# USB.net
KiCad netlist of a schematic drawn in Altium Designer
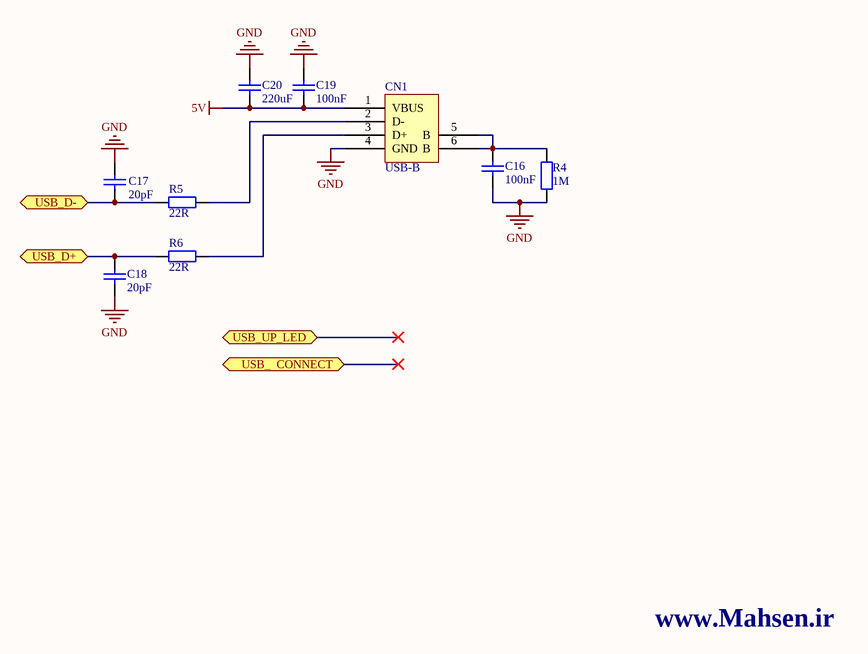
[diagram p0: USB.SchDoc]

(export (version "E")
  (design (tool "Eeschema 10.0.6"))
  (components
    (comp (ref "C16")
      (value "100nF")
      (footprint "0805")
      (description "Capacitor")
      (fields (field (name "PUBLISHER") "Altium Limited"))
      (libsource (lib "Miscellaneous Devices") (part "Cap"))
    )
    (comp (ref "C17")
      (value "20pF")
      (footprint "0805")
      (description "Capacitor")
      (fields (field (name "PUBLISHER") "Altium Limited"))
      (libsource (lib "Miscellaneous Devices") (part "Cap"))
    )
    (comp (ref "C18")
      (value "20pF")
      (footprint "0805")
      (description "Capacitor")
      (fields (field (name "PUBLISHER") "Altium Limited"))
      (libsource (lib "Miscellaneous Devices") (part "Cap"))
    )
    (comp (ref "C19")
      (value "100nF")
      (footprint "0805")
      (description "Capacitor")
      (fields (field (name "PUBLISHER") "Altium Limited"))
      (libsource (lib "Miscellaneous Devices") (part "Cap"))
    )
    (comp (ref "C20")
      (value "220uF")
      (footprint "0805")
      (description "Capacitor")
      (fields (field (name "PUBLISHER") "Altium Limited"))
      (libsource (lib "Miscellaneous Devices") (part "Cap"))
    )
    (comp (ref "CN1") (value "USB-B") (footprint "CONN_USB") (libsource (lib "Lotfi") (part "USB-B")))
    (comp (ref "R4")
      (value "1M")
      (footprint "0805")
      (description "Resistor")
      (fields (field (name "PUBLISHER") "Altium Limited"))
      (libsource (lib "Miscellaneous Devices") (part "Res2"))
    )
    (comp (ref "R5")
      (value "22R")
      (footprint "0805")
      (description "Resistor")
      (fields (field (name "PUBLISHER") "Altium Limited"))
      (libsource (lib "") (part "Res2_1"))
    )
    (comp (ref "R6")
      (value "22R")
      (footprint "0805")
      (description "Resistor")
      (fields (field (name "PUBLISHER") "Altium Limited"))
      (libsource (lib "") (part "Res2_1"))
    )
  )
  (nets
    (net (code "2") (name "/USB_D+") (class "Default")
      (node (ref "C18") (pin "1") (pinfunction "1_1") (pintype "passive"))
      (node (ref "R6") (pin "2") (pinfunction "2_2") (pintype "passive"))
    )
    (net (code "3") (name "/USB_D-") (class "Default")
      (node (ref "C17") (pin "2") (pinfunction "2_2") (pintype "passive"))
      (node (ref "R5") (pin "2") (pinfunction "2_2") (pintype "passive"))
    )
    (net (code "5") (name "5V") (class "Default")
      (node (ref "C19") (pin "2") (pinfunction "2_2") (pintype "passive"))
      (node (ref "C20") (pin "2") (pinfunction "2_2") (pintype "passive"))
      (node (ref "CN1") (pin "1") (pinfunction "VBUS_1") (pintype "passive"))
    )
    (net (code "6") (name "GND") (class "Default")
      (node (ref "C16") (pin "2") (pinfunction "2_2") (pintype "passive"))
      (node (ref "C17") (pin "1") (pinfunction "1_1") (pintype "passive"))
      (node (ref "C18") (pin "2") (pinfunction "2_2") (pintype "passive"))
      (node (ref "C19") (pin "1") (pinfunction "1_1") (pintype "passive"))
      (node (ref "C20") (pin "1") (pinfunction "1_1") (pintype "passive"))
      (node (ref "CN1") (pin "4") (pinfunction "GND_4") (pintype "passive"))
      (node (ref "R4") (pin "1") (pinfunction "1_1") (pintype "passive"))
    )
    (net (code "7") (name "Net-(C16-Pad1)") (class "Default")
      (node (ref "C16") (pin "1") (pinfunction "1_1") (pintype "passive"))
      (node (ref "CN1") (pin "5") (pinfunction "B_5") (pintype "passive"))
      (node (ref "CN1") (pin "6") (pinfunction "B_6") (pintype "passive"))
      (node (ref "R4") (pin "2") (pinfunction "2_2") (pintype "passive"))
    )
    (net (code "8") (name "Net-(CN1-D+)") (class "Default")
      (node (ref "CN1") (pin "3") (pinfunction "D+_3") (pintype "passive"))
      (node (ref "R6") (pin "1") (pinfunction "1_1") (pintype "passive"))
    )
    (net (code "9") (name "Net-(CN1-D-)") (class "Default")
      (node (ref "CN1") (pin "2") (pinfunction "D-_2") (pintype "passive"))
      (node (ref "R5") (pin "1") (pinfunction "1_1") (pintype "passive"))
    )
  )
)
